# BLE.net
KiCad netlist of a schematic drawn in Altium Designer
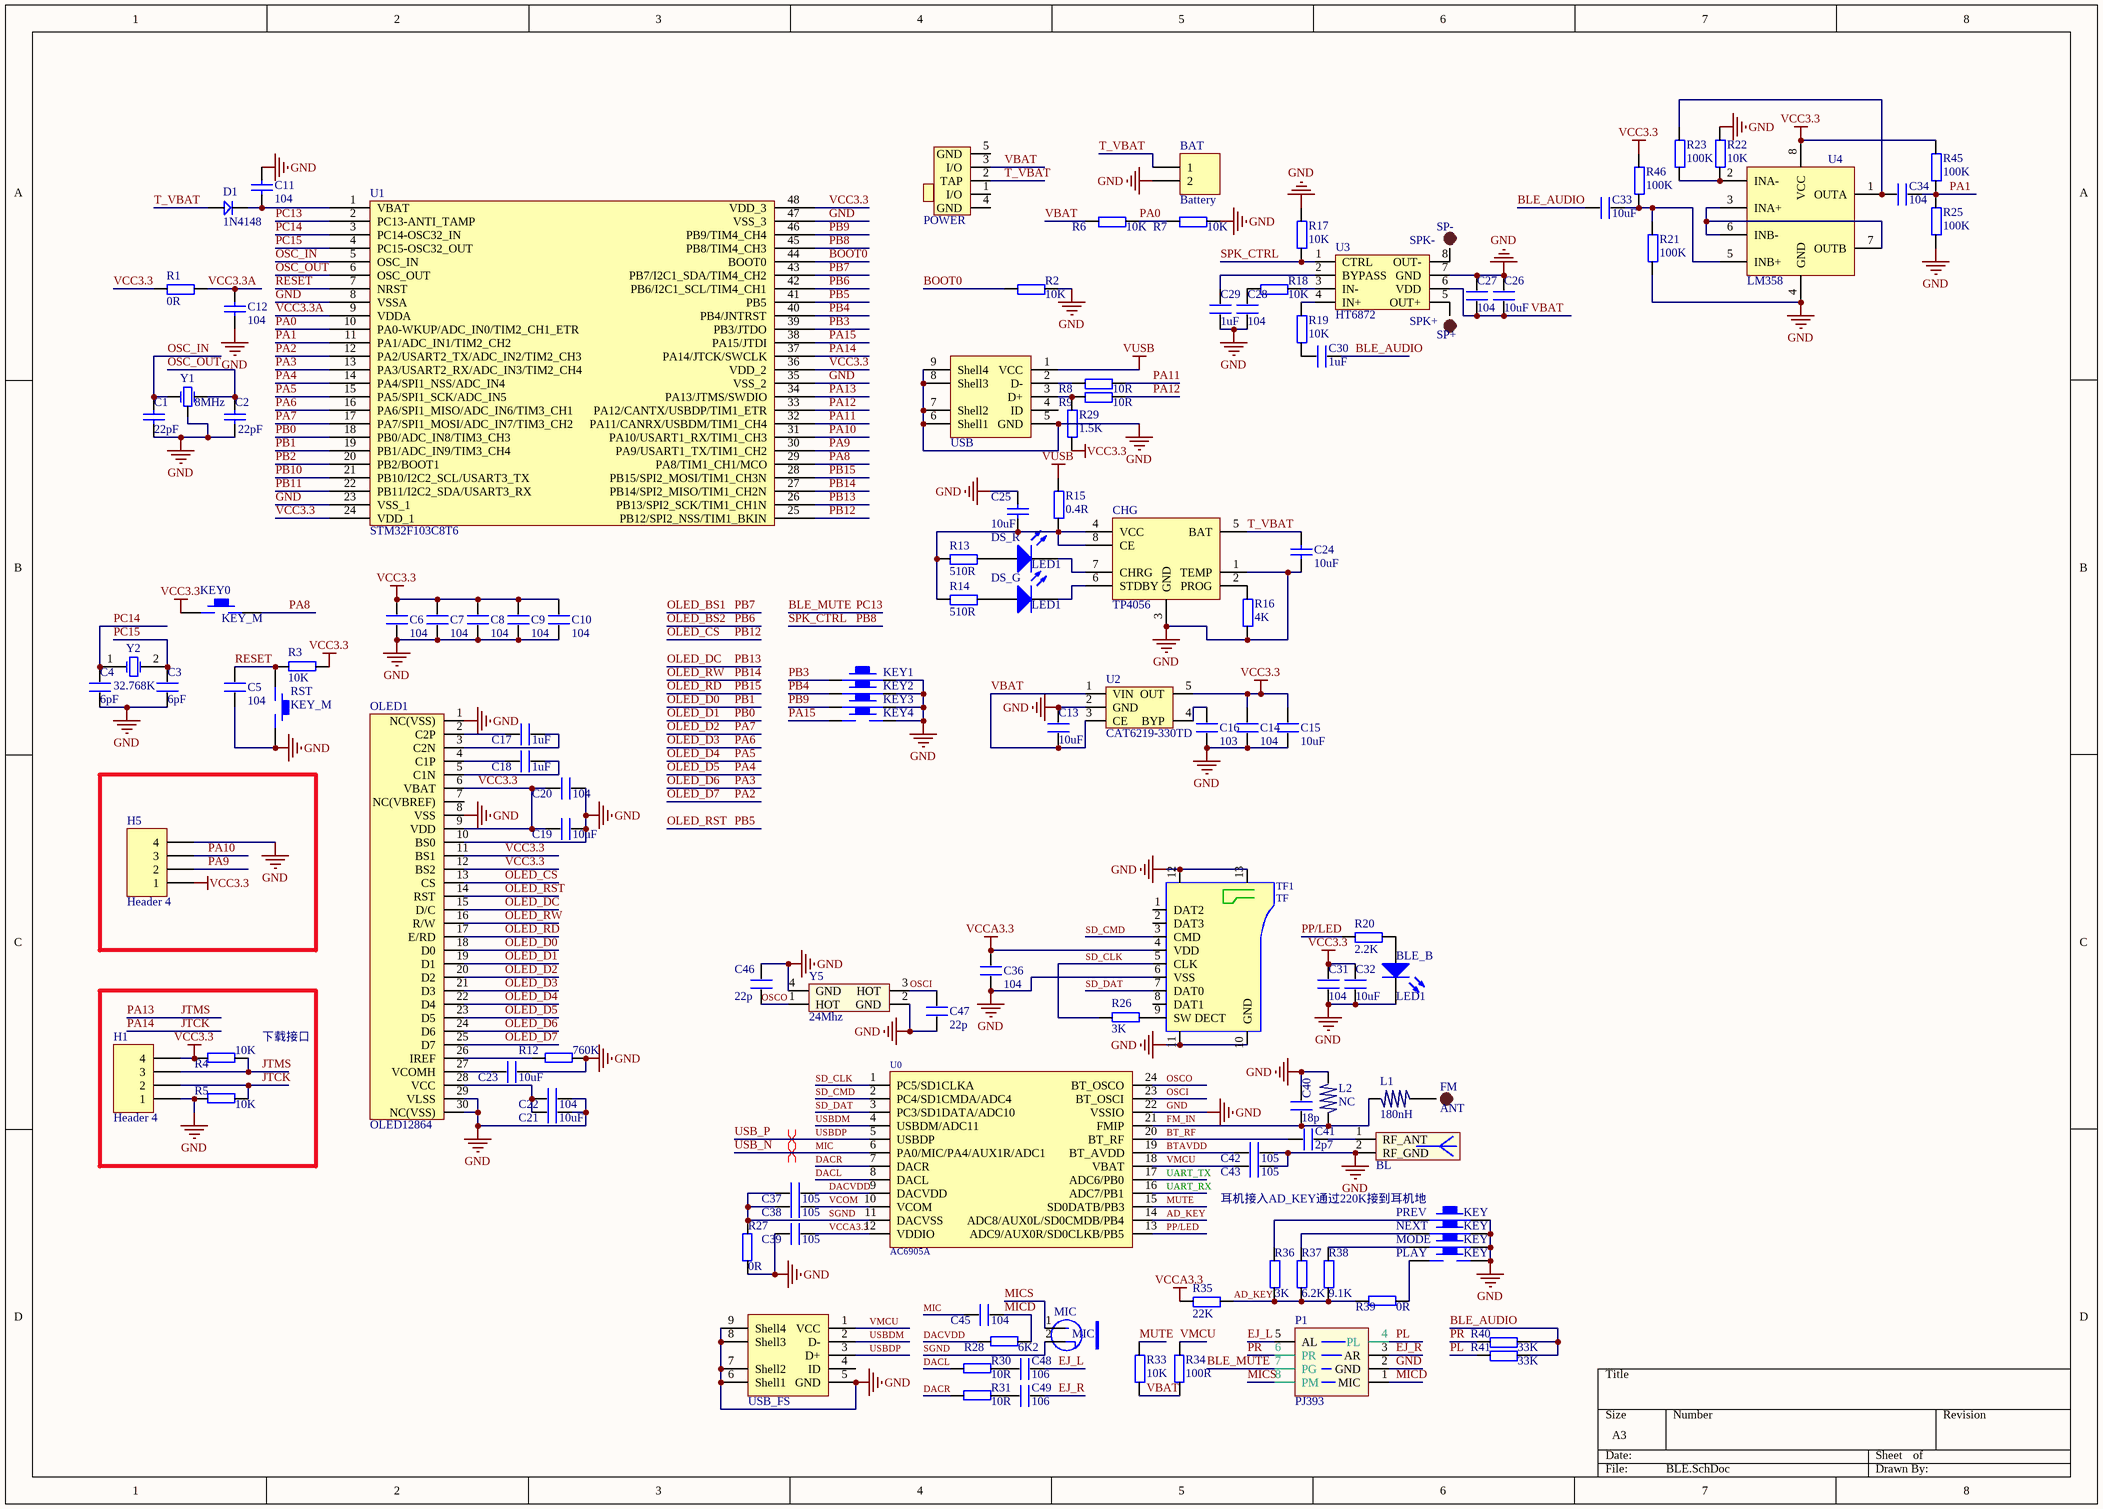
[diagram p0: BLE.SchDoc]

(export (version "E")
  (design (tool "Eeschema 10.0.6"))
  (components
    (comp (ref "BAT")
      (value "Battery")
      (footprint "HDR2.54-LI-2P")
      (description "Header, 2-Pin")
      (fields (field (name "PUBLISHER") "Altium Limited"))
      (libsource (lib "WarShip V3 STM32103封装库") (part "Header 2"))
    )
    (comp (ref "BL")
      (value "ANT-2.4G")
      (footprint "BT_ANT")
      (description "ANT,2.4G,PCB天线")
      (libsource (lib "ALIENTEK_W601_Board_V1.51") (part "ANT-2.4G"))
    )
    (comp (ref "BLE_B")
      (value "LED1")
      (footprint "LED 0805B")
      (description "Typical RED, GREEN, YELLOW, AMBER GaAs LED")
      (fields (field (name "PUBLISHER") "Altium Limited"))
      (libsource (lib "阿波罗STM32F4&F7底板封装库") (part "LED2"))
    )
    (comp (ref "C1") (value "22pF") (footprint "C 0603_M") (libsource (lib "L476") (part "CAP")))
    (comp (ref "C2") (value "22pF") (footprint "C 0603_M") (libsource (lib "L476") (part "CAP")))
    (comp (ref "C3")
      (value "6pF")
      (footprint "C 0603_M")
      (libsource (lib "WarShip V3 STM32103封装库") (part "C"))
    )
    (comp (ref "C4")
      (value "6pF")
      (footprint "C 0603_M")
      (libsource (lib "WarShip V3 STM32103封装库") (part "C"))
    )
    (comp (ref "C5")
      (value "104")
      (footprint "C 0603_M")
      (libsource (lib "WarShip V3 STM32103封装库") (part "C"))
    )
    (comp (ref "C6")
      (value "104")
      (footprint "C 0603_M")
      (libsource (lib "WarShip V3 STM32103封装库") (part "C"))
    )
    (comp (ref "C7")
      (value "104")
      (footprint "C 0603_M")
      (libsource (lib "WarShip V3 STM32103封装库") (part "C"))
    )
    (comp (ref "C8")
      (value "104")
      (footprint "C 0603_M")
      (libsource (lib "WarShip V3 STM32103封装库") (part "C"))
    )
    (comp (ref "C9")
      (value "104")
      (footprint "C 0603_M")
      (libsource (lib "WarShip V3 STM32103封装库") (part "C"))
    )
    (comp (ref "C10")
      (value "104")
      (footprint "C 0603_M")
      (libsource (lib "WarShip V3 STM32103封装库") (part "C"))
    )
    (comp (ref "C11") (value "104") (footprint "C 0603_M") (libsource (lib "L476") (part "CAP")))
    (comp (ref "C12") (value "104") (footprint "C 0603_M") (libsource (lib "L476") (part "CAP")))
    (comp (ref "C13")
      (value "10uF")
      (footprint "C 0603_M")
      (libsource (lib "WarShip V3 STM32103封装库") (part "C"))
    )
    (comp (ref "C14")
      (value "104")
      (footprint "C 0603_M")
      (libsource (lib "WarShip V3 STM32103封装库") (part "C"))
    )
    (comp (ref "C15")
      (value "10uF")
      (footprint "C 0603_M")
      (libsource (lib "WarShip V3 STM32103封装库") (part "C"))
    )
    (comp (ref "C16")
      (value "103")
      (footprint "C 0603_M")
      (libsource (lib "WarShip V3 STM32103封装库") (part "C"))
    )
    (comp (ref "C17")
      (value "1uF")
      (footprint "C 0603_M")
      (libsource (lib "WarShip V3 STM32103封装库") (part "C"))
    )
    (comp (ref "C18")
      (value "1uF")
      (footprint "C 0603_M")
      (libsource (lib "WarShip V3 STM32103封装库") (part "C"))
    )
    (comp (ref "C19")
      (value "10uF")
      (footprint "C 0603_M")
      (libsource (lib "WarShip V3 STM32103封装库") (part "C"))
    )
    (comp (ref "C20")
      (value "104")
      (footprint "C 0603_M")
      (libsource (lib "WarShip V3 STM32103封装库") (part "C"))
    )
    (comp (ref "C21")
      (value "10uF")
      (footprint "C 0603_M")
      (libsource (lib "WarShip V3 STM32103封装库") (part "C"))
    )
    (comp (ref "C22")
      (value "104")
      (footprint "C 0603_M")
      (libsource (lib "WarShip V3 STM32103封装库") (part "C"))
    )
    (comp (ref "C23")
      (value "10uF")
      (footprint "C 0603_M")
      (libsource (lib "WarShip V3 STM32103封装库") (part "C"))
    )
    (comp (ref "C24") (value "10uF") (footprint "C 0603_M") (libsource (lib "L476") (part "CAP")))
    (comp (ref "C25") (value "10uF") (footprint "C 0603_M") (libsource (lib "L476") (part "CAP")))
    (comp (ref "C26")
      (value "10uF")
      (footprint "C 0603_M")
      (libsource (lib "WarShip V3 STM32103封装库") (part "C"))
    )
    (comp (ref "C27")
      (value "104")
      (footprint "C 0603_M")
      (libsource (lib "WarShip V3 STM32103封装库") (part "C"))
    )
    (comp (ref "C28")
      (value "104")
      (footprint "C 0603_M")
      (libsource (lib "WarShip V3 STM32103封装库") (part "C"))
    )
    (comp (ref "C29")
      (value "1uF")
      (footprint "C 0603_M")
      (libsource (lib "WarShip V3 STM32103封装库") (part "C"))
    )
    (comp (ref "C30") (value "1uF") (footprint "C 0603_M") (libsource (lib "MYCOMLIB") (part "C")))
    (comp (ref "C31")
      (value "104")
      (footprint "C 0603_M")
      (libsource (lib "WarShip V3 STM32103封装库") (part "C"))
    )
    (comp (ref "C32")
      (value "10uF")
      (footprint "C 0603_M")
      (libsource (lib "WarShip V3 STM32103封装库") (part "C"))
    )
    (comp (ref "C33") (value "10uF") (footprint "C 0603_M") (libsource (lib "MYCOMLIB") (part "C")))
    (comp (ref "C34") (value "104") (footprint "C 0603_M") (libsource (lib "MYCOMLIB") (part "C")))
    (comp (ref "C36")
      (value "104")
      (footprint "C 0603_M")
      (libsource (lib "WarShip V3 STM32103封装库") (part "C"))
    )
    (comp (ref "C37")
      (value "105")
      (footprint "C 0603_M")
      (libsource (lib "WarShip V3 STM32103封装库") (part "C"))
    )
    (comp (ref "C38")
      (value "105")
      (footprint "C 0603_M")
      (libsource (lib "WarShip V3 STM32103封装库") (part "C"))
    )
    (comp (ref "C39")
      (value "105")
      (footprint "C 0603_M")
      (libsource (lib "WarShip V3 STM32103封装库") (part "C"))
    )
    (comp (ref "C40")
      (value "18p")
      (footprint "C 0603_M")
      (libsource (lib "WarShip V3 STM32103封装库") (part "C"))
    )
    (comp (ref "C41")
      (value "2p7")
      (footprint "C 0603_M")
      (libsource (lib "WarShip V3 STM32103封装库") (part "C"))
    )
    (comp (ref "C42")
      (value "105")
      (footprint "C 0603_M")
      (libsource (lib "WarShip V3 STM32103封装库") (part "C"))
    )
    (comp (ref "C43")
      (value "105")
      (footprint "C 0603_M")
      (libsource (lib "WarShip V3 STM32103封装库") (part "C"))
    )
    (comp (ref "C45")
      (value "104")
      (footprint "C 0603_M")
      (libsource (lib "WarShip V3 STM32103封装库") (part "C"))
    )
    (comp (ref "C46")
      (value "22p")
      (footprint "C 0603_M")
      (libsource (lib "WarShip V3 STM32103封装库") (part "C"))
    )
    (comp (ref "C47")
      (value "22p")
      (footprint "C 0603_M")
      (libsource (lib "WarShip V3 STM32103封装库") (part "C"))
    )
    (comp (ref "C48")
      (value "106")
      (footprint "C 0603_M")
      (libsource (lib "WarShip V3 STM32103封装库") (part "C"))
    )
    (comp (ref "C49")
      (value "106")
      (footprint "C 0603_M")
      (libsource (lib "WarShip V3 STM32103封装库") (part "C"))
    )
    (comp (ref "CHG") (value "TP4056") (footprint "SOP8_M") (libsource (lib "tp4056") (part "Component_1")))
    (comp (ref "D1")
      (value "1N4148")
      (footprint "DIODE_SOP")
      (libsource (lib "阿波罗STM32F4&F7底板封装库") (part "D"))
    )
    (comp (ref "DS_G")
      (value "LED1")
      (footprint "LED 0805G")
      (description "Typical RED, GREEN, YELLOW, AMBER GaAs LED")
      (fields (field (name "PUBLISHER") "Altium Limited"))
      (libsource (lib "阿波罗STM32F4&F7底板封装库") (part "LED2"))
    )
    (comp (ref "DS_R")
      (value "LED1")
      (footprint "LED 0805R")
      (description "Typical RED, GREEN, YELLOW, AMBER GaAs LED")
      (fields (field (name "PUBLISHER") "Altium Limited"))
      (libsource (lib "阿波罗STM32F4&F7底板封装库") (part "LED2"))
    )
    (comp (ref "FM")
      (value "ANT")
      (footprint "TP-1.5")
      (description "测试点")
      (libsource (lib "阿波罗STM32F4&F7&H7底板封装库") (part "TEST-POINT"))
    )
    (comp (ref "H1")
      (value "Header 4")
      (footprint "HDR2.54-LI-4P")
      (description "Header, 4-Pin")
      (fields (field (name "PUBLISHER") "Altium Limited"))
      (libsource (lib "WarShip V3 STM32103封装库") (part "Header 4"))
    )
    (comp (ref "H5")
      (value "Header 4")
      (footprint "HDR2.54-LI-4P")
      (description "Header, 4-Pin")
      (fields (field (name "PUBLISHER") "Altium Limited"))
      (libsource (lib "WarShip V3 STM32103封装库") (part "Header 4"))
    )
    (comp (ref "KEY0") (value "KEY_M") (footprint "TSW SMD-3*6*2.5") (libsource (lib "") (part "KEY_M_1")))
    (comp (ref "KEY1")
      (value "S-KEY-SMD-324225")
      (footprint "KEY-SOP324225")
      (description "KEY,SMD,324225")
      (libsource (lib "Pandora_STM32L4_Board_V2.4") (part "S-KEY-SMD-324225"))
    )
    (comp (ref "KEY2")
      (value "S-KEY-SMD-324225")
      (footprint "KEY-SOP324225")
      (description "KEY,SMD,324225")
      (libsource (lib "Pandora_STM32L4_Board_V2.4") (part "S-KEY-SMD-324225"))
    )
    (comp (ref "KEY3")
      (value "S-KEY-SMD-324225")
      (footprint "KEY-SOP324225")
      (description "KEY,SMD,324225")
      (libsource (lib "Pandora_STM32L4_Board_V2.4") (part "S-KEY-SMD-324225"))
    )
    (comp (ref "KEY4")
      (value "S-KEY-SMD-324225")
      (footprint "KEY-SOP324225")
      (description "KEY,SMD,324225")
      (libsource (lib "Pandora_STM32L4_Board_V2.4") (part "S-KEY-SMD-324225"))
    )
    (comp (ref "L1") (value "180nH") (footprint "L 0603") (libsource (lib "") (part "L_1")))
    (comp (ref "L2") (value "NC") (footprint "L 0603") (libsource (lib "阿波罗STM32F4&F7底板封装库") (part "L")))
    (comp (ref "MIC") (value "MIC") (footprint "mic6022") (libsource (lib "ATK-VS1053 MP3") (part "MIC")))
    (comp (ref "MODE") (value "KEY") (footprint "TSW SMD-3*6*2.5") (libsource (lib "") (part "KEY_M_1")))
    (comp (ref "NEXT") (value "KEY") (footprint "TSW SMD-3*6*2.5") (libsource (lib "") (part "KEY_M_1")))
    (comp (ref "OLED1")
      (value "OLED12864")
      (footprint "OLED_0.96")
      (libsource (lib "OLED模块封装库") (part "OLED12864"))
    )
    (comp (ref "P1") (value "PJ393") (footprint "PJ393") (libsource (lib "tp4056") (part "PJ393")))
    (comp (ref "PLAY") (value "KEY") (footprint "TSW SMD-3*6*2.5") (libsource (lib "") (part "KEY_M_1")))
    (comp (ref "POWER")
      (value "BUTTON_DIP3")
      (footprint "MSK-12C01-07")
      (description "拨动开关SS-12F44")
      (libsource (lib "Pandora_STM32L4_Board_V2.4") (part "BUTTON_DIP3"))
    )
    (comp (ref "PREV") (value "KEY") (footprint "TSW SMD-3*6*2.5") (libsource (lib "") (part "KEY_M_1")))
    (comp (ref "R1")
      (value "0R")
      (footprint "R 0603_M")
      (libsource (lib "WarShip V3 STM32103封装库") (part "R"))
    )
    (comp (ref "R2")
      (value "10K")
      (footprint "R 0603_M")
      (libsource (lib "WarShip V3 STM32103封装库") (part "R"))
    )
    (comp (ref "R3")
      (value "10K")
      (footprint "R 0603_M")
      (libsource (lib "WarShip V3 STM32103封装库") (part "R"))
    )
    (comp (ref "R4")
      (value "10K")
      (footprint "R 0603_M")
      (libsource (lib "WarShip V3 STM32103封装库") (part "R"))
    )
    (comp (ref "R5")
      (value "10K")
      (footprint "R 0603_M")
      (libsource (lib "WarShip V3 STM32103封装库") (part "R"))
    )
    (comp (ref "R6")
      (value "10K")
      (footprint "R 0603_M")
      (libsource (lib "WarShip V3 STM32103封装库") (part "R"))
    )
    (comp (ref "R7")
      (value "10K")
      (footprint "R 0603_M")
      (libsource (lib "WarShip V3 STM32103封装库") (part "R"))
    )
    (comp (ref "R8")
      (value "10R")
      (footprint "R 0603_M")
      (libsource (lib "WarShip V3 STM32103封装库") (part "R"))
    )
    (comp (ref "R9")
      (value "10R")
      (footprint "R 0603_M")
      (libsource (lib "WarShip V3 STM32103封装库") (part "R"))
    )
    (comp (ref "R12")
      (value "760K")
      (footprint "R 0603_M")
      (libsource (lib "WarShip V3 STM32103封装库") (part "R"))
    )
    (comp (ref "R13")
      (value "510R")
      (footprint "R 0603_M")
      (libsource (lib "WarShip V3 STM32103封装库") (part "R"))
    )
    (comp (ref "R14")
      (value "510R")
      (footprint "R 0603_M")
      (libsource (lib "WarShip V3 STM32103封装库") (part "R"))
    )
    (comp (ref "R15")
      (value "0.4R")
      (footprint "R 0603_M")
      (libsource (lib "WarShip V3 STM32103封装库") (part "R"))
    )
    (comp (ref "R16")
      (value "4K")
      (footprint "R 0603_M")
      (libsource (lib "WarShip V3 STM32103封装库") (part "R"))
    )
    (comp (ref "R17") (value "10K") (footprint "R 0603_M") (libsource (lib "ALIENTEK_COMPONENT") (part "R")))
    (comp (ref "R18") (value "10K") (footprint "R 0603_M") (libsource (lib "ALIENTEK_COMPONENT") (part "R")))
    (comp (ref "R19") (value "10K") (footprint "R 0603_M") (libsource (lib "ALIENTEK_COMPONENT") (part "R")))
    (comp (ref "R20")
      (value "2.2K")
      (footprint "R 0603_M")
      (libsource (lib "WarShip V3 STM32103封装库") (part "R"))
    )
    (comp (ref "R21") (value "100K") (footprint "R 0603_M") (libsource (lib "ALIENTEK_COMPONENT") (part "R")))
    (comp (ref "R22") (value "10K") (footprint "R 0603_M") (libsource (lib "ALIENTEK_COMPONENT") (part "R")))
    (comp (ref "R23") (value "100K") (footprint "R 0603_M") (libsource (lib "ALIENTEK_COMPONENT") (part "R")))
    (comp (ref "R25") (value "100K") (footprint "R 0603_M") (libsource (lib "ALIENTEK_COMPONENT") (part "R")))
    (comp (ref "R26")
      (value "3K")
      (footprint "R 0603_M")
      (libsource (lib "WarShip V3 STM32103封装库") (part "R"))
    )
    (comp (ref "R27")
      (value "0R")
      (footprint "R 0603_M")
      (libsource (lib "WarShip V3 STM32103封装库") (part "R"))
    )
    (comp (ref "R28")
      (value "6K2")
      (footprint "R 0603_M")
      (libsource (lib "WarShip V3 STM32103封装库") (part "R"))
    )
    (comp (ref "R29")
      (value "1.5K")
      (footprint "R 0603_M")
      (libsource (lib "WarShip V3 STM32103封装库") (part "R"))
    )
    (comp (ref "R30")
      (value "10R")
      (footprint "R 0603_M")
      (libsource (lib "WarShip V3 STM32103封装库") (part "R"))
    )
    (comp (ref "R31")
      (value "10R")
      (footprint "R 0603_M")
      (libsource (lib "WarShip V3 STM32103封装库") (part "R"))
    )
    (comp (ref "R33")
      (value "10K")
      (footprint "R 0603_M")
      (libsource (lib "WarShip V3 STM32103封装库") (part "R"))
    )
    (comp (ref "R34")
      (value "100R")
      (footprint "R 0603_M")
      (libsource (lib "WarShip V3 STM32103封装库") (part "R"))
    )
    (comp (ref "R35")
      (value "22K")
      (footprint "R 0603_M")
      (libsource (lib "WarShip V3 STM32103封装库") (part "R"))
    )
    (comp (ref "R36")
      (value "3K")
      (footprint "R 0603_M")
      (libsource (lib "WarShip V3 STM32103封装库") (part "R"))
    )
    (comp (ref "R37")
      (value "6.2K")
      (footprint "R 0603_M")
      (libsource (lib "WarShip V3 STM32103封装库") (part "R"))
    )
    (comp (ref "R38")
      (value "9.1K")
      (footprint "R 0603_M")
      (libsource (lib "WarShip V3 STM32103封装库") (part "R"))
    )
    (comp (ref "R39")
      (value "0R")
      (footprint "R 0603_M")
      (libsource (lib "WarShip V3 STM32103封装库") (part "R"))
    )
    (comp (ref "R40")
      (value "33K")
      (footprint "R 0603_M")
      (libsource (lib "WarShip V3 STM32103封装库") (part "R"))
    )
    (comp (ref "R41")
      (value "33K")
      (footprint "R 0603_M")
      (libsource (lib "WarShip V3 STM32103封装库") (part "R"))
    )
    (comp (ref "R45") (value "100K") (footprint "R 0603_M") (libsource (lib "ALIENTEK_COMPONENT") (part "R")))
    (comp (ref "R46") (value "100K") (footprint "R 0603_M") (libsource (lib "ALIENTEK_COMPONENT") (part "R")))
    (comp (ref "RST")
      (value "KEY_M")
      (footprint "TSW SMD-3*6*2.5")
      (libsource (lib "STM32F429核心板封装库") (part "KEY_M"))
    )
    (comp (ref "SP+")
      (value "SPK+")
      (footprint "TP-1.5")
      (description "测试点")
      (libsource (lib "ALIENTEK_COMPONENT") (part "TEST-POINT"))
    )
    (comp (ref "SP-")
      (value "SPK-")
      (footprint "TP-1.5")
      (description "测试点")
      (libsource (lib "ALIENTEK_COMPONENT") (part "TEST-POINT"))
    )
    (comp (ref "TF1") (value "TF") (footprint "TF") (libsource (lib "AC6905A") (part "TF")))
    (comp (ref "U0")
      (value "AC6905A")
      (footprint "SSOP24")
      (libsource (lib "AC6905A") (part "Component_1_1"))
    )
    (comp (ref "U1")
      (value "STM32F103C8T6")
      (footprint "LQFP-48PIN")
      (libsource (lib "Pandora_STM32L4_Board_V2.4") (part "U-STM32F103C8T6"))
    )
    (comp (ref "U2")
      (value "CAT6219-330TD")
      (footprint "SOT23-5L")
      (description "3.3V 500mA LDO")
      (libsource (lib "STM32H743核心板封装库") (part "CAT6219-330TD"))
    )
    (comp (ref "U3")
      (value "HT6872")
      (footprint "SOP8_M")
      (description "HT6871")
      (libsource (lib "WarShip V3 STM32103封装库") (part "HT6871"))
    )
    (comp (ref "U4") (value "LM358") (footprint "SOP8_M") (libsource (lib "tp4056") (part "Component_2")))
    (comp (ref "USB")
      (value "J-MICRO-USB-5S")
      (footprint "USB-AB-5S")
      (description "Micro USB 5.9有柱脚长1.25加长针")
      (libsource (lib "Pandora_STM32L4_Board_V2.4") (part "J-MICRO-USB-5S"))
    )
    (comp (ref "USB_FS")
      (value "J-MICRO-USB-5S")
      (footprint "USB-AB-5S")
      (description "Micro USB 5.9有柱脚长1.25加长针")
      (libsource (lib "Pandora_STM32L4_Board_V2.4") (part "J-MICRO-USB-5S"))
    )
    (comp (ref "Y1")
      (value "8MHz")
      (footprint "Y-XTAL-3215-3P")
      (description "XTAL,3215,8MHz")
      (libsource (lib "Pandora_STM32L4_Board_V2.4") (part "Y-3215-8M"))
    )
    (comp (ref "Y2")
      (value "32.768K")
      (footprint "OSC 3215-2P")
      (description "Crystal Oscillator")
      (fields (field (name "PUBLISHER") "Altium Limited"))
      (libsource (lib "WarShip V3 STM32103封装库") (part "XTAL"))
    )
    (comp (ref "Y5")
      (value "24Mhz")
      (footprint "OSC 3225-4P")
      (description "3225贴片无源晶振")
      (libsource (lib "STM32F767核心板封装库") (part "XTAL_3225"))
    )
  )
  (nets
    (net (code "1") (name "/AD_KEY") (class "Default")
      (node (ref "R35") (pin "2") (pintype "passive"))
      (node (ref "R36") (pin "1") (pintype "passive"))
      (node (ref "R37") (pin "1") (pintype "passive"))
      (node (ref "R38") (pin "1") (pintype "passive"))
      (node (ref "R39") (pin "2") (pintype "passive"))
      (node (ref "U0") (pin "14") (pinfunction "ADC8/AUX0L/SD0CMDB/PB4_14") (pintype "passive"))
    )
    (net (code "2") (name "/BLE_AUDIO") (class "Default")
      (node (ref "C30") (pin "2") (pintype "passive"))
      (node (ref "C33") (pin "1") (pintype "passive"))
      (node (ref "R40") (pin "2") (pintype "passive"))
      (node (ref "R41") (pin "2") (pintype "passive"))
    )
    (net (code "3") (name "/BLE_MUTE") (class "Default")
      (node (ref "P1") (pin "7") (pinfunction "PG_7") (pintype "passive"))
      (node (ref "U1") (pin "2") (pinfunction "PC13-ANTI_TAMP_2") (pintype "passive"))
    )
    (net (code "4") (name "/BOOT0") (class "Default")
      (node (ref "R2") (pin "1") (pintype "passive"))
      (node (ref "U1") (pin "44") (pinfunction "BOOT0_44") (pintype "passive"))
    )
    (net (code "5") (name "/BTAVDD") (class "Default")
      (node (ref "C42") (pin "1") (pintype "passive"))
      (node (ref "U0") (pin "19") (pinfunction "BT_AVDD_19") (pintype "passive"))
    )
    (net (code "6") (name "/BT_RF") (class "Default")
      (node (ref "C41") (pin "1") (pintype "passive"))
      (node (ref "U0") (pin "20") (pinfunction "BT_RF_20") (pintype "passive"))
    )
    (net (code "7") (name "/DACL") (class "Default")
      (node (ref "R30") (pin "2") (pintype "passive"))
      (node (ref "U0") (pin "8") (pinfunction "DACL_8") (pintype "passive"))
    )
    (net (code "8") (name "/DACR") (class "Default")
      (node (ref "R31") (pin "2") (pintype "passive"))
      (node (ref "U0") (pin "7") (pinfunction "DACR_7") (pintype "passive"))
    )
    (net (code "9") (name "/DACVDD") (class "Default")
      (node (ref "C37") (pin "1") (pintype "passive"))
      (node (ref "R28") (pin "2") (pintype "passive"))
      (node (ref "U0") (pin "9") (pinfunction "DACVDD_9") (pintype "passive"))
    )
    (net (code "10") (name "/EJ_L") (class "Default")
      (node (ref "C48") (pin "2") (pintype "passive"))
      (node (ref "P1") (pin "5") (pinfunction "AL_5") (pintype "passive"))
    )
    (net (code "11") (name "/EJ_R") (class "Default")
      (node (ref "C49") (pin "2") (pintype "passive"))
      (node (ref "P1") (pin "3") (pinfunction "AR_3") (pintype "passive"))
    )
    (net (code "12") (name "/FM_IN") (class "Default")
      (node (ref "C40") (pin "2") (pintype "passive"))
      (node (ref "L1") (pin "1") (pintype "passive"))
      (node (ref "L2") (pin "2") (pintype "passive"))
      (node (ref "U0") (pin "21") (pinfunction "FMIP_21") (pintype "passive"))
    )
    (net (code "13") (name "/JTCK") (class "Default")
      (node (ref "H1") (pin "2") (pinfunction "2_2") (pintype "passive"))
      (node (ref "R5") (pin "1") (pintype "passive"))
      (node (ref "U1") (pin "37") (pinfunction "PA14/JTCK/SWCLK_37") (pintype "passive"))
    )
    (net (code "14") (name "/JTMS") (class "Default")
      (node (ref "H1") (pin "3") (pinfunction "3_3") (pintype "passive"))
      (node (ref "R4") (pin "1") (pintype "passive"))
      (node (ref "U1") (pin "34") (pinfunction "PA13/JTMS/SWDIO_34") (pintype "passive"))
    )
    (net (code "15") (name "/MIC") (class "Default")
      (node (ref "C45") (pin "1") (pintype "passive"))
      (node (ref "U0") (pin "6") (pinfunction "PA0/MIC/PA4/AUX1R/ADC1_6") (pintype "passive"))
    )
    (net (code "16") (name "/MICD") (class "Default")
      (node (ref "C45") (pin "2") (pintype "passive"))
      (node (ref "P1") (pin "1") (pinfunction "MIC_1") (pintype "passive"))
      (node (ref "R28") (pin "1") (pintype "passive"))
    )
    (net (code "17") (name "/MICS") (class "Default")
      (node (ref "MIC") (pin "1") (pinfunction "VCC_1") (pintype "passive"))
      (node (ref "P1") (pin "8") (pinfunction "PM_8") (pintype "passive"))
    )
    (net (code "18") (name "/MUTE") (class "Default")
      (node (ref "R33") (pin "2") (pintype "passive"))
      (node (ref "U0") (pin "15") (pinfunction "SD0DATB/PB3_15") (pintype "passive"))
    )
    (net (code "19") (name "/OLED_BS1") (class "Default")
      (node (ref "U1") (pin "43") (pinfunction "PB7/I2C1_SDA/TIM4_CH2_43") (pintype "passive"))
    )
    (net (code "20") (name "/OLED_BS2") (class "Default")
      (node (ref "U1") (pin "42") (pinfunction "PB6/I2C1_SCL/TIM4_CH1_42") (pintype "passive"))
    )
    (net (code "21") (name "/OLED_CS") (class "Default")
      (node (ref "OLED1") (pin "13") (pinfunction "CS_13") (pintype "passive"))
      (node (ref "U1") (pin "25") (pinfunction "PB12/SPI2_NSS/TIM1_BKIN_25") (pintype "passive"))
    )
    (net (code "22") (name "/OLED_D0") (class "Default")
      (node (ref "OLED1") (pin "18") (pinfunction "D0_18") (pintype "passive"))
      (node (ref "U1") (pin "19") (pinfunction "PB1/ADC_IN9/TIM3_CH4_19") (pintype "passive"))
    )
    (net (code "23") (name "/OLED_D1") (class "Default")
      (node (ref "OLED1") (pin "19") (pinfunction "D1_19") (pintype "passive"))
      (node (ref "U1") (pin "18") (pinfunction "PB0/ADC_IN8/TIM3_CH3_18") (pintype "passive"))
    )
    (net (code "24") (name "/OLED_D2") (class "Default")
      (node (ref "OLED1") (pin "20") (pinfunction "D2_20") (pintype "passive"))
      (node (ref "U1") (pin "17") (pinfunction "PA7/SPI1_MOSI/ADC_IN7/TIM3_CH2_17") (pintype "passive"))
    )
    (net (code "25") (name "/OLED_D3") (class "Default")
      (node (ref "OLED1") (pin "21") (pinfunction "D3_21") (pintype "passive"))
      (node (ref "U1") (pin "16") (pinfunction "PA6/SPI1_MISO/ADC_IN6/TIM3_CH1_16") (pintype "passive"))
    )
    (net (code "26") (name "/OLED_D4") (class "Default")
      (node (ref "OLED1") (pin "22") (pinfunction "D4_22") (pintype "passive"))
      (node (ref "U1") (pin "15") (pinfunction "PA5/SPI1_SCK/ADC_IN5_15") (pintype "passive"))
    )
    (net (code "27") (name "/OLED_D5") (class "Default")
      (node (ref "OLED1") (pin "23") (pinfunction "D5_23") (pintype "passive"))
      (node (ref "U1") (pin "14") (pinfunction "PA4/SPI1_NSS/ADC_IN4_14") (pintype "passive"))
    )
    (net (code "28") (name "/OLED_D6") (class "Default")
      (node (ref "OLED1") (pin "24") (pinfunction "D6_24") (pintype "passive"))
      (node (ref "U1") (pin "13") (pinfunction "PA3/USART2_RX/ADC_IN3/TIM2_CH4_13") (pintype "passive"))
    )
    (net (code "29") (name "/OLED_D7") (class "Default")
      (node (ref "OLED1") (pin "25") (pinfunction "D7_25") (pintype "passive"))
      (node (ref "U1") (pin "12") (pinfunction "PA2/USART2_TX/ADC_IN2/TIM2_CH3_12") (pintype "passive"))
    )
    (net (code "30") (name "/OLED_DC") (class "Default")
      (node (ref "OLED1") (pin "15") (pinfunction "D/C_15") (pintype "passive"))
      (node (ref "U1") (pin "26") (pinfunction "PB13/SPI2_SCK/TIM1_CH1N_26") (pintype "passive"))
    )
    (net (code "31") (name "/OLED_RD") (class "Default")
      (node (ref "OLED1") (pin "17") (pinfunction "E/RD_17") (pintype "passive"))
      (node (ref "U1") (pin "28") (pinfunction "PB15/SPI2_MOSI/TIM1_CH3N_28") (pintype "passive"))
    )
    (net (code "32") (name "/OLED_RST") (class "Default")
      (node (ref "OLED1") (pin "14") (pinfunction "RST_14") (pintype "passive"))
      (node (ref "U1") (pin "41") (pinfunction "PB5_41") (pintype "passive"))
    )
    (net (code "33") (name "/OLED_RW") (class "Default")
      (node (ref "OLED1") (pin "16") (pinfunction "R/W_16") (pintype "passive"))
      (node (ref "U1") (pin "27") (pinfunction "PB14/SPI2_MISO/TIM1_CH2N_27") (pintype "passive"))
    )
    (net (code "34") (name "/OSCI") (class "Default")
      (node (ref "C47") (pin "2") (pintype "passive"))
      (node (ref "U0") (pin "23") (pinfunction "BT_OSCI_23") (pintype "passive"))
      (node (ref "Y5") (pin "3") (pinfunction "HOT_3") (pintype "passive"))
    )
    (net (code "35") (name "/OSCO") (class "Default")
      (node (ref "C46") (pin "2") (pintype "passive"))
      (node (ref "U0") (pin "24") (pinfunction "BT_OSCO_24") (pintype "passive"))
      (node (ref "Y5") (pin "1") (pinfunction "HOT_1") (pintype "passive"))
    )
    (net (code "36") (name "/OSC_IN") (class "Default")
      (node (ref "C1") (pin "2") (pinfunction "2_2") (pintype "passive"))
      (node (ref "U1") (pin "5") (pinfunction "OSC_IN_5") (pintype "passive"))
      (node (ref "Y1") (pin "1") (pinfunction "OSC1_1") (pintype "passive"))
    )
    (net (code "37") (name "/OSC_OUT") (class "Default")
      (node (ref "C2") (pin "2") (pinfunction "2_2") (pintype "passive"))
      (node (ref "U1") (pin "6") (pinfunction "OSC_OUT_6") (pintype "passive"))
      (node (ref "Y1") (pin "3") (pinfunction "OSC2_3") (pintype "passive"))
    )
    (net (code "38") (name "/PA0") (class "Default")
      (node (ref "R6") (pin "2") (pintype "passive"))
      (node (ref "R7") (pin "1") (pintype "passive"))
      (node (ref "U1") (pin "10") (pinfunction "PA0-WKUP/ADC_IN0/TIM2_CH1_ETR_10") (pintype "passive"))
    )
    (net (code "39") (name "/PA1") (class "Default")
      (node (ref "C34") (pin "2") (pintype "passive"))
      (node (ref "R25") (pin "2") (pintype "passive"))
      (node (ref "R45") (pin "1") (pintype "passive"))
      (node (ref "U1") (pin "11") (pinfunction "PA1/ADC_IN1/TIM2_CH2_11") (pintype "passive"))
    )
    (net (code "40") (name "/PA8") (class "Default")
      (node (ref "KEY0") (pin "2") (pinfunction "2_2") (pintype "passive"))
      (node (ref "U1") (pin "29") (pinfunction "PA8/TIM1_CH1/MCO_29") (pintype "passive"))
    )
    (net (code "41") (name "/PA9") (class "Default")
      (node (ref "H5") (pin "2") (pinfunction "2_2") (pintype "passive"))
      (node (ref "U1") (pin "30") (pinfunction "PA9/USART1_TX/TIM1_CH2_30") (pintype "passive"))
    )
    (net (code "42") (name "/PA10") (class "Default")
      (node (ref "H5") (pin "3") (pinfunction "3_3") (pintype "passive"))
      (node (ref "U1") (pin "31") (pinfunction "PA10/USART1_RX/TIM1_CH3_31") (pintype "passive"))
    )
    (net (code "43") (name "/PA11") (class "Default")
      (node (ref "R8") (pin "2") (pintype "passive"))
      (node (ref "U1") (pin "32") (pinfunction "PA11/CANRX/USBDM/TIM1_CH4_32") (pintype "passive"))
    )
    (net (code "44") (name "/PA12") (class "Default")
      (node (ref "R9") (pin "2") (pintype "passive"))
      (node (ref "U1") (pin "33") (pinfunction "PA12/CANTX/USBDP/TIM1_ETR_33") (pintype "passive"))
    )
    (net (code "45") (name "/PA15") (class "Default")
      (node (ref "KEY4") (pin "1") (pinfunction "1_1") (pintype "passive"))
      (node (ref "U1") (pin "38") (pinfunction "PA15/JTDI_38") (pintype "passive"))
    )
    (net (code "46") (name "/PB2") (class "Default")
      (node (ref "U1") (pin "20") (pinfunction "PB2/BOOT1_20") (pintype "passive"))
    )
    (net (code "47") (name "/PB3") (class "Default")
      (node (ref "KEY1") (pin "1") (pinfunction "1_1") (pintype "passive"))
      (node (ref "U1") (pin "39") (pinfunction "PB3/JTDO_39") (pintype "passive"))
    )
    (net (code "48") (name "/PB4") (class "Default")
      (node (ref "KEY2") (pin "1") (pinfunction "1_1") (pintype "passive"))
      (node (ref "U1") (pin "40") (pinfunction "PB4/JNTRST_40") (pintype "passive"))
    )
    (net (code "49") (name "/PB8") (class "Default")
      (node (ref "R17") (pin "1") (pintype "passive"))
      (node (ref "U1") (pin "45") (pinfunction "PB8/TIM4_CH3_45") (pintype "passive"))
      (node (ref "U3") (pin "1") (pinfunction "CTRL_1") (pintype "passive"))
    )
    (net (code "50") (name "/PB9") (class "Default")
      (node (ref "KEY3") (pin "1") (pinfunction "1_1") (pintype "passive"))
      (node (ref "U1") (pin "46") (pinfunction "PB9/TIM4_CH4_46") (pintype "passive"))
    )
    (net (code "51") (name "/PB10") (class "Default")
      (node (ref "U1") (pin "21") (pinfunction "PB10/I2C2_SCL/USART3_TX_21") (pintype "passive"))
    )
    (net (code "52") (name "/PB11") (class "Default")
      (node (ref "U1") (pin "22") (pinfunction "PB11/I2C2_SDA/USART3_RX_22") (pintype "passive"))
    )
    (net (code "53") (name "/PC14") (class "Default")
      (node (ref "C4") (pin "2") (pintype "passive"))
      (node (ref "U1") (pin "3") (pinfunction "PC14-OSC32_IN_3") (pintype "passive"))
      (node (ref "Y2") (pin "1") (pinfunction "OSC1_1") (pintype "passive"))
    )
    (net (code "54") (name "/PC15") (class "Default")
      (node (ref "C3") (pin "2") (pintype "passive"))
      (node (ref "U1") (pin "4") (pinfunction "PC15-OSC32_OUT_4") (pintype "passive"))
      (node (ref "Y2") (pin "2") (pinfunction "OSC2_2") (pintype "passive"))
    )
    (net (code "55") (name "/PL") (class "Default")
      (node (ref "P1") (pin "4") (pinfunction "PL_4") (pintype "passive"))
      (node (ref "R41") (pin "1") (pintype "passive"))
    )
    (net (code "56") (name "/PP{slash}LED") (class "Default")
      (node (ref "R20") (pin "1") (pintype "passive"))
      (node (ref "U0") (pin "13") (pinfunction "ADC9/AUX0R/SD0CLKB/PB5_13") (pintype "passive"))
    )
    (net (code "57") (name "/PR") (class "Default")
      (node (ref "P1") (pin "6") (pinfunction "PR_6") (pintype "passive"))
      (node (ref "R40") (pin "1") (pintype "passive"))
    )
    (net (code "58") (name "/RESET") (class "Default")
      (node (ref "C5") (pin "2") (pintype "passive"))
      (node (ref "R3") (pin "2") (pintype "passive"))
      (node (ref "RST") (pin "1") (pinfunction "1_1") (pintype "passive"))
      (node (ref "U1") (pin "7") (pinfunction "NRST_7") (pintype "passive"))
    )
    (net (code "59") (name "/SD_CLK") (class "Default")
      (node (ref "R26") (pin "2") (pintype "passive"))
      (node (ref "TF1") (pin "5") (pinfunction "CLK_5") (pintype "passive"))
      (node (ref "U0") (pin "1") (pinfunction "PC5/SD1CLKA_1") (pintype "passive"))
    )
    (net (code "60") (name "/SD_CMD") (class "Default")
      (node (ref "TF1") (pin "3") (pinfunction "CMD_3") (pintype "passive"))
      (node (ref "U0") (pin "2") (pinfunction "PC4/SD1CMDA/ADC4_2") (pintype "passive"))
    )
    (net (code "61") (name "/SD_DAT") (class "Default")
      (node (ref "TF1") (pin "7") (pinfunction "DAT0_7") (pintype "passive"))
      (node (ref "U0") (pin "3") (pinfunction "PC3/SD1DATA/ADC10_3") (pintype "passive"))
    )
    (net (code "62") (name "/SGND") (class "Default")
      (node (ref "C37") (pin "2") (pintype "passive"))
      (node (ref "C38") (pin "2") (pintype "passive"))
      (node (ref "MIC") (pin "2") (pinfunction "GND_2") (pintype "passive"))
      (node (ref "R27") (pin "1") (pintype "passive"))
      (node (ref "U0") (pin "11") (pinfunction "DACVSS_11") (pintype "passive"))
    )
    (net (code "63") (name "/T_VBAT") (class "Default")
      (node (ref "BAT") (pin "1") (pinfunction "1_1") (pintype "passive"))
      (node (ref "C24") (pin "1") (pinfunction "1_1") (pintype "passive"))
      (node (ref "CHG") (pin "5") (pinfunction "BAT_5") (pintype "passive"))
      (node (ref "D1") (pin "1") (pintype "passive"))
      (node (ref "POWER") (pin "2") (pinfunction "TAP_2") (pintype "passive"))
    )
    (net (code "64") (name "/UART_RX") (class "Default")
      (node (ref "U0") (pin "16") (pinfunction "ADC7/PB1_16") (pintype "passive"))
    )
    (net (code "65") (name "/UART_TX") (class "Default")
      (node (ref "U0") (pin "17") (pinfunction "ADC6/PB0_17") (pintype "passive"))
    )
    (net (code "66") (name "/USBDM") (class "Default")
      (node (ref "U0") (pin "4") (pinfunction "USBDM/ADC11_4") (pintype "passive"))
      (node (ref "USB_FS") (pin "2") (pinfunction "D-_2") (pintype "passive"))
    )
    (net (code "67") (name "/USBDP") (class "Default")
      (node (ref "U0") (pin "5") (pinfunction "USBDP_5") (pintype "passive"))
      (node (ref "USB_FS") (pin "3") (pinfunction "D+_3") (pintype "passive"))
    )
    (net (code "68") (name "/VBAT") (class "Default")
      (node (ref "C13") (pin "1") (pintype "passive"))
      (node (ref "C26") (pin "1") (pintype "passive"))
      (node (ref "C27") (pin "1") (pintype "passive"))
      (node (ref "POWER") (pin "3") (pinfunction "I/O_3") (pintype "passive"))
      (node (ref "R33") (pin "1") (pintype "passive"))
      (node (ref "R34") (pin "2") (pintype "passive"))
      (node (ref "R6") (pin "1") (pintype "passive"))
      (node (ref "U2") (pin "1") (pinfunction "VIN_1") (pintype "passive"))
      (node (ref "U2") (pin "3") (pinfunction "CE_3") (pintype "passive"))
      (node (ref "U3") (pin "6") (pinfunction "VDD_6") (pintype "passive"))
    )
    (net (code "69") (name "/VCC3.3A") (class "Default")
      (node (ref "C12") (pin "2") (pinfunction "2_2") (pintype "passive"))
      (node (ref "R1") (pin "2") (pintype "passive"))
      (node (ref "U1") (pin "9") (pinfunction "VDDA_9") (pintype "passive"))
    )
    (net (code "70") (name "/VCOM") (class "Default")
      (node (ref "C38") (pin "1") (pintype "passive"))
      (node (ref "U0") (pin "10") (pinfunction "VCOM_10") (pintype "passive"))
    )
    (net (code "71") (name "/VMCU") (class "Default")
      (node (ref "C43") (pin "1") (pintype "passive"))
      (node (ref "R34") (pin "1") (pintype "passive"))
      (node (ref "U0") (pin "18") (pinfunction "VBAT_18") (pintype "passive"))
      (node (ref "USB_FS") (pin "1") (pinfunction "VCC_1") (pintype "passive"))
    )
    (net (code "72") (name "GND") (class "Default")
      (node (ref "BAT") (pin "2") (pinfunction "2_2") (pintype "passive"))
      (node (ref "BL") (pin "2") (pinfunction "RF_GND_2") (pintype "passive"))
      (node (ref "BLE_B") (pin "2") (pinfunction "K_2") (pintype "passive"))
      (node (ref "C1") (pin "1") (pinfunction "1_1") (pintype "passive"))
      (node (ref "C10") (pin "1") (pintype "passive"))
      (node (ref "C11") (pin "2") (pinfunction "2_2") (pintype "passive"))
      (node (ref "C12") (pin "1") (pinfunction "1_1") (pintype "passive"))
      (node (ref "C13") (pin "2") (pintype "passive"))
      (node (ref "C14") (pin "1") (pintype "passive"))
      (node (ref "C15") (pin "1") (pintype "passive"))
      (node (ref "C16") (pin "1") (pintype "passive"))
      (node (ref "C19") (pin "1") (pintype "passive"))
      (node (ref "C2") (pin "1") (pinfunction "1_1") (pintype "passive"))
      (node (ref "C20") (pin "1") (pintype "passive"))
      (node (ref "C21") (pin "1") (pintype "passive"))
      (node (ref "C22") (pin "1") (pintype "passive"))
      (node (ref "C23") (pin "1") (pintype "passive"))
      (node (ref "C24") (pin "2") (pinfunction "2_2") (pintype "passive"))
      (node (ref "C25") (pin "2") (pinfunction "2_2") (pintype "passive"))
      (node (ref "C26") (pin "2") (pintype "passive"))
      (node (ref "C27") (pin "2") (pintype "passive"))
      (node (ref "C28") (pin "1") (pintype "passive"))
      (node (ref "C29") (pin "1") (pintype "passive"))
      (node (ref "C3") (pin "1") (pintype "passive"))
      (node (ref "C31") (pin "1") (pintype "passive"))
      (node (ref "C32") (pin "1") (pintype "passive"))
      (node (ref "C36") (pin "1") (pintype "passive"))
      (node (ref "C39") (pin "2") (pintype "passive"))
      (node (ref "C4") (pin "1") (pintype "passive"))
      (node (ref "C40") (pin "1") (pintype "passive"))
      (node (ref "C42") (pin "2") (pintype "passive"))
      (node (ref "C43") (pin "2") (pintype "passive"))
      (node (ref "C46") (pin "1") (pintype "passive"))
      (node (ref "C47") (pin "1") (pintype "passive"))
      (node (ref "C5") (pin "1") (pintype "passive"))
      (node (ref "C6") (pin "1") (pintype "passive"))
      (node (ref "C7") (pin "1") (pintype "passive"))
      (node (ref "C8") (pin "1") (pintype "passive"))
      (node (ref "C9") (pin "1") (pintype "passive"))
      (node (ref "CHG") (pin "1") (pinfunction "TEMP_1") (pintype "passive"))
      (node (ref "CHG") (pin "3") (pinfunction "GND_3") (pintype "passive"))
      (node (ref "H1") (pin "1") (pinfunction "1_1") (pintype "passive"))
      (node (ref "H5") (pin "4") (pinfunction "4_4") (pintype "passive"))
      (node (ref "KEY1") (pin "2") (pinfunction "2_2") (pintype "passive"))
      (node (ref "KEY2") (pin "2") (pinfunction "2_2") (pintype "passive"))
      (node (ref "KEY3") (pin "2") (pinfunction "2_2") (pintype "passive"))
      (node (ref "KEY4") (pin "2") (pinfunction "2_2") (pintype "passive"))
      (node (ref "L2") (pin "1") (pintype "passive"))
      (node (ref "MODE") (pin "2") (pinfunction "2_2") (pintype "passive"))
      (node (ref "NEXT") (pin "2") (pinfunction "2_2") (pintype "passive"))
      (node (ref "OLED1") (pin "1") (pinfunction "NC(VSS)_1") (pintype "passive"))
      (node (ref "OLED1") (pin "10") (pinfunction "BS0_10") (pintype "passive"))
      (node (ref "OLED1") (pin "29") (pinfunction "VLSS_29") (pintype "passive"))
      (node (ref "OLED1") (pin "30") (pinfunction "NC(VSS)_30") (pintype "passive"))
      (node (ref "OLED1") (pin "8") (pinfunction "VSS_8") (pintype "passive"))
      (node (ref "P1") (pin "2") (pinfunction "GND_2") (pintype "passive"))
      (node (ref "PLAY") (pin "2") (pinfunction "2_2") (pintype "passive"))
      (node (ref "PREV") (pin "2") (pinfunction "2_2") (pintype "passive"))
      (node (ref "R12") (pin "1") (pintype "passive"))
      (node (ref "R16") (pin "1") (pintype "passive"))
      (node (ref "R17") (pin "2") (pintype "passive"))
      (node (ref "R2") (pin "2") (pintype "passive"))
      (node (ref "R21") (pin "1") (pintype "passive"))
      (node (ref "R22") (pin "2") (pintype "passive"))
      (node (ref "R25") (pin "1") (pintype "passive"))
      (node (ref "R27") (pin "2") (pintype "passive"))
      (node (ref "R5") (pin "2") (pintype "passive"))
      (node (ref "R7") (pin "2") (pintype "passive"))
      (node (ref "RST") (pin "2") (pinfunction "2_2") (pintype "passive"))
      (node (ref "TF1") (pin "10") (pinfunction "GND_10") (pintype "passive"))
      (node (ref "TF1") (pin "11") (pintype "passive"))
      (node (ref "TF1") (pin "12") (pintype "passive"))
      (node (ref "TF1") (pin "13") (pintype "passive"))
      (node (ref "TF1") (pin "6") (pinfunction "VSS_6") (pintype "passive"))
      (node (ref "U0") (pin "22") (pinfunction "VSSIO_22") (pintype "passive"))
      (node (ref "U1") (pin "23") (pinfunction "VSS_1_23") (pintype "passive"))
      (node (ref "U1") (pin "35") (pinfunction "VSS_2_35") (pintype "passive"))
      (node (ref "U1") (pin "47") (pinfunction "VSS_3_47") (pintype "passive"))
      (node (ref "U1") (pin "8") (pinfunction "VSSA_8") (pintype "passive"))
      (node (ref "U2") (pin "2") (pinfunction "GND_2") (pintype "passive"))
      (node (ref "U3") (pin "7") (pinfunction "GND_7") (pintype "passive"))
      (node (ref "U4") (pin "4") (pinfunction "GND_4") (pintype "passive"))
      (node (ref "USB") (pin "5") (pinfunction "GND_5") (pintype "passive"))
      (node (ref "USB") (pin "6") (pinfunction "Shell1_6") (pintype "passive"))
      (node (ref "USB") (pin "7") (pinfunction "Shell2_7") (pintype "passive"))
      (node (ref "USB") (pin "8") (pinfunction "Shell3_8") (pintype "passive"))
      (node (ref "USB") (pin "9") (pinfunction "Shell4_9") (pintype "passive"))
      (node (ref "USB_FS") (pin "5") (pinfunction "GND_5") (pintype "passive"))
      (node (ref "USB_FS") (pin "6") (pinfunction "Shell1_6") (pintype "passive"))
      (node (ref "USB_FS") (pin "7") (pinfunction "Shell2_7") (pintype "passive"))
      (node (ref "USB_FS") (pin "8") (pinfunction "Shell3_8") (pintype "passive"))
      (node (ref "USB_FS") (pin "9") (pinfunction "Shell4_9") (pintype "passive"))
      (node (ref "Y1") (pin "2") (pinfunction "GND_2") (pintype "passive"))
      (node (ref "Y5") (pin "2") (pinfunction "GND_2") (pintype "passive"))
      (node (ref "Y5") (pin "4") (pinfunction "GND_4") (pintype "passive"))
    )
    (net (code "73") (name "Net-(BL-RF_ANT)") (class "Default")
      (node (ref "BL") (pin "1") (pinfunction "RF_ANT_1") (pintype "passive"))
      (node (ref "C41") (pin "2") (pintype "passive"))
    )
    (net (code "74") (name "Net-(BLE_B-A)") (class "Default")
      (node (ref "BLE_B") (pin "1") (pinfunction "A_1") (pintype "passive"))
      (node (ref "R20") (pin "2") (pintype "passive"))
    )
    (net (code "75") (name "Net-(C28-Pad2)") (class "Default")
      (node (ref "C28") (pin "2") (pintype "passive"))
      (node (ref "R18") (pin "1") (pintype "passive"))
    )
    (net (code "76") (name "Net-(C30-Pad1)") (class "Default")
      (node (ref "C30") (pin "1") (pintype "passive"))
      (node (ref "R19") (pin "1") (pintype "passive"))
    )
    (net (code "77") (name "Net-(C48-Pad1)") (class "Default")
      (node (ref "C48") (pin "1") (pintype "passive"))
      (node (ref "R30") (pin "1") (pintype "passive"))
    )
    (net (code "78") (name "Net-(C49-Pad1)") (class "Default")
      (node (ref "C49") (pin "1") (pintype "passive"))
      (node (ref "R31") (pin "1") (pintype "passive"))
    )
    (net (code "79") (name "Net-(CHG-CE)") (class "Default")
      (node (ref "C25") (pin "1") (pinfunction "1_1") (pintype "passive"))
      (node (ref "CHG") (pin "4") (pinfunction "VCC_4") (pintype "passive"))
      (node (ref "CHG") (pin "8") (pinfunction "CE_8") (pintype "passive"))
      (node (ref "R13") (pin "1") (pintype "passive"))
      (node (ref "R14") (pin "1") (pintype "passive"))
      (node (ref "R15") (pin "1") (pintype "passive"))
    )
    (net (code "80") (name "Net-(CHG-CHRG)") (class "Default")
      (node (ref "CHG") (pin "7") (pinfunction "CHRG_7") (pintype "passive"))
      (node (ref "DS_R") (pin "2") (pinfunction "K_2") (pintype "passive"))
    )
    (net (code "81") (name "Net-(CHG-PROG)") (class "Default")
      (node (ref "CHG") (pin "2") (pinfunction "PROG_2") (pintype "passive"))
      (node (ref "R16") (pin "2") (pintype "passive"))
    )
    (net (code "82") (name "Net-(CHG-STDBY)") (class "Default")
      (node (ref "CHG") (pin "6") (pinfunction "STDBY_6") (pintype "passive"))
      (node (ref "DS_G") (pin "2") (pinfunction "K_2") (pintype "passive"))
    )
    (net (code "83") (name "Net-(DS_G-A)") (class "Default")
      (node (ref "DS_G") (pin "1") (pinfunction "A_1") (pintype "passive"))
      (node (ref "R14") (pin "2") (pintype "passive"))
    )
    (net (code "84") (name "Net-(DS_R-A)") (class "Default")
      (node (ref "DS_R") (pin "1") (pinfunction "A_1") (pintype "passive"))
      (node (ref "R13") (pin "2") (pintype "passive"))
    )
    (net (code "85") (name "Net-(FM-Pad1)") (class "Default")
      (node (ref "FM") (pin "1") (pinfunction "1_1") (pintype "passive"))
      (node (ref "L1") (pin "2") (pintype "passive"))
    )
    (net (code "86") (name "Net-(MODE-Pad1)") (class "Default")
      (node (ref "MODE") (pin "1") (pinfunction "1_1") (pintype "passive"))
      (node (ref "R38") (pin "2") (pintype "passive"))
    )
    (net (code "87") (name "Net-(NEXT-Pad1)") (class "Default")
      (node (ref "NEXT") (pin "1") (pinfunction "1_1") (pintype "passive"))
      (node (ref "R37") (pin "2") (pintype "passive"))
    )
    (net (code "88") (name "Net-(OLED1-C1N)") (class "Default")
      (node (ref "C18") (pin "1") (pintype "passive"))
      (node (ref "OLED1") (pin "5") (pinfunction "C1N_5") (pintype "passive"))
    )
    (net (code "89") (name "Net-(OLED1-C1P)") (class "Default")
      (node (ref "C18") (pin "2") (pintype "passive"))
      (node (ref "OLED1") (pin "4") (pinfunction "C1P_4") (pintype "passive"))
    )
    (net (code "90") (name "Net-(OLED1-C2N)") (class "Default")
      (node (ref "C17") (pin "1") (pintype "passive"))
      (node (ref "OLED1") (pin "3") (pinfunction "C2N_3") (pintype "passive"))
    )
    (net (code "91") (name "Net-(OLED1-C2P)") (class "Default")
      (node (ref "C17") (pin "2") (pintype "passive"))
      (node (ref "OLED1") (pin "2") (pinfunction "C2P_2") (pintype "passive"))
    )
    (net (code "92") (name "Net-(OLED1-IREF)") (class "Default")
      (node (ref "OLED1") (pin "26") (pinfunction "IREF_26") (pintype "passive"))
      (node (ref "R12") (pin "2") (pintype "passive"))
    )
    (net (code "93") (name "Net-(OLED1-VCC)") (class "Default")
      (node (ref "C21") (pin "2") (pintype "passive"))
      (node (ref "C22") (pin "2") (pintype "passive"))
      (node (ref "OLED1") (pin "28") (pinfunction "VCC_28") (pintype "passive"))
    )
    (net (code "94") (name "Net-(OLED1-VCOMH)") (class "Default")
      (node (ref "C23") (pin "2") (pintype "passive"))
      (node (ref "OLED1") (pin "27") (pinfunction "VCOMH_27") (pintype "passive"))
    )
    (net (code "95") (name "Net-(PLAY-Pad1)") (class "Default")
      (node (ref "PLAY") (pin "1") (pinfunction "1_1") (pintype "passive"))
      (node (ref "R39") (pin "1") (pintype "passive"))
    )
    (net (code "96") (name "Net-(PREV-Pad1)") (class "Default")
      (node (ref "PREV") (pin "1") (pinfunction "1_1") (pintype "passive"))
      (node (ref "R36") (pin "2") (pintype "passive"))
    )
    (net (code "97") (name "Net-(TF1-SW_DECT)") (class "Default")
      (node (ref "R26") (pin "1") (pintype "passive"))
      (node (ref "TF1") (pin "9") (pinfunction "SW_DECT_9") (pintype "passive"))
    )
    (net (code "98") (name "Net-(U1-VBAT)") (class "Default")
      (node (ref "C11") (pin "1") (pinfunction "1_1") (pintype "passive"))
      (node (ref "D1") (pin "2") (pintype "passive"))
      (node (ref "U1") (pin "1") (pinfunction "VBAT_1") (pintype "passive"))
    )
    (net (code "99") (name "Net-(U2-BYP)") (class "Default")
      (node (ref "C16") (pin "2") (pintype "passive"))
      (node (ref "U2") (pin "4") (pinfunction "BYP_4") (pintype "passive"))
    )
    (net (code "100") (name "Net-(U3-BYPASS)") (class "Default")
      (node (ref "C29") (pin "2") (pintype "passive"))
      (node (ref "U3") (pin "2") (pinfunction "BYPASS_2") (pintype "passive"))
    )
    (net (code "101") (name "Net-(U3-IN+)") (class "Default")
      (node (ref "R19") (pin "2") (pintype "passive"))
      (node (ref "U3") (pin "4") (pinfunction "IN+_4") (pintype "passive"))
    )
    (net (code "102") (name "Net-(U3-IN-)") (class "Default")
      (node (ref "R18") (pin "2") (pintype "passive"))
      (node (ref "U3") (pin "3") (pinfunction "IN-_3") (pintype "passive"))
    )
    (net (code "103") (name "Net-(U3-OUT+)") (class "Default")
      (node (ref "SP+") (pin "1") (pinfunction "1_1") (pintype "passive"))
      (node (ref "U3") (pin "5") (pinfunction "OUT+_5") (pintype "passive"))
    )
    (net (code "104") (name "Net-(U3-OUT-)") (class "Default")
      (node (ref "SP-") (pin "1") (pinfunction "1_1") (pintype "passive"))
      (node (ref "U3") (pin "8") (pinfunction "OUT-_8") (pintype "passive"))
    )
    (net (code "105") (name "Net-(U4-INA+)") (class "Default")
      (node (ref "U4") (pin "3") (pinfunction "INA+_3") (pintype "passive"))
      (node (ref "U4") (pin "6") (pinfunction "INB-_6") (pintype "passive"))
      (node (ref "U4") (pin "7") (pinfunction "OUTB_7") (pintype "passive"))
    )
    (net (code "106") (name "Net-(U4-INA-)") (class "Default")
      (node (ref "R22") (pin "1") (pintype "passive"))
      (node (ref "R23") (pin "1") (pintype "passive"))
      (node (ref "U4") (pin "2") (pinfunction "INA-_2") (pintype "passive"))
    )
    (net (code "107") (name "Net-(U4-INB+)") (class "Default")
      (node (ref "C33") (pin "2") (pintype "passive"))
      (node (ref "R21") (pin "2") (pintype "passive"))
      (node (ref "R46") (pin "1") (pintype "passive"))
      (node (ref "U4") (pin "5") (pinfunction "INB+_5") (pintype "passive"))
    )
    (net (code "108") (name "Net-(U4-OUTA)") (class "Default")
      (node (ref "C34") (pin "1") (pintype "passive"))
      (node (ref "R23") (pin "2") (pintype "passive"))
      (node (ref "U4") (pin "1") (pinfunction "OUTA_1") (pintype "passive"))
    )
    (net (code "109") (name "Net-(USB-D+)") (class "Default")
      (node (ref "R29") (pin "2") (pintype "passive"))
      (node (ref "R9") (pin "1") (pintype "passive"))
      (node (ref "USB") (pin "3") (pinfunction "D+_3") (pintype "passive"))
    )
    (net (code "110") (name "Net-(USB-D-)") (class "Default")
      (node (ref "R8") (pin "1") (pintype "passive"))
      (node (ref "USB") (pin "2") (pinfunction "D-_2") (pintype "passive"))
    )
    (net (code "111") (name "VCC3.3") (class "Default")
      (node (ref "C10") (pin "2") (pintype "passive"))
      (node (ref "C14") (pin "2") (pintype "passive"))
      (node (ref "C15") (pin "2") (pintype "passive"))
      (node (ref "C19") (pin "2") (pintype "passive"))
      (node (ref "C20") (pin "2") (pintype "passive"))
      (node (ref "C31") (pin "2") (pintype "passive"))
      (node (ref "C32") (pin "2") (pintype "passive"))
      (node (ref "C6") (pin "2") (pintype "passive"))
      (node (ref "C7") (pin "2") (pintype "passive"))
      (node (ref "C8") (pin "2") (pintype "passive"))
      (node (ref "C9") (pin "2") (pintype "passive"))
      (node (ref "H1") (pin "4") (pinfunction "4_4") (pintype "passive"))
      (node (ref "H5") (pin "1") (pinfunction "1_1") (pintype "passive"))
      (node (ref "KEY0") (pin "1") (pinfunction "1_1") (pintype "passive"))
      (node (ref "OLED1") (pin "11") (pinfunction "BS1_11") (pintype "passive"))
      (node (ref "OLED1") (pin "12") (pinfunction "BS2_12") (pintype "passive"))
      (node (ref "OLED1") (pin "6") (pinfunction "VBAT_6") (pintype "passive"))
      (node (ref "OLED1") (pin "9") (pinfunction "VDD_9") (pintype "passive"))
      (node (ref "R1") (pin "1") (pintype "passive"))
      (node (ref "R29") (pin "1") (pintype "passive"))
      (node (ref "R3") (pin "1") (pintype "passive"))
      (node (ref "R4") (pin "2") (pintype "passive"))
      (node (ref "R45") (pin "2") (pintype "passive"))
      (node (ref "R46") (pin "2") (pintype "passive"))
      (node (ref "U1") (pin "24") (pinfunction "VDD_1_24") (pintype "passive"))
      (node (ref "U1") (pin "36") (pinfunction "VDD_2_36") (pintype "passive"))
      (node (ref "U1") (pin "48") (pinfunction "VDD_3_48") (pintype "passive"))
      (node (ref "U2") (pin "5") (pinfunction "OUT_5") (pintype "passive"))
      (node (ref "U4") (pin "8") (pinfunction "VCC_8") (pintype "passive"))
    )
    (net (code "112") (name "VCCA3.3") (class "Default")
      (node (ref "C36") (pin "2") (pintype "passive"))
      (node (ref "C39") (pin "1") (pintype "passive"))
      (node (ref "R35") (pin "1") (pintype "passive"))
      (node (ref "TF1") (pin "4") (pinfunction "VDD_4") (pintype "passive"))
      (node (ref "U0") (pin "12") (pinfunction "VDDIO_12") (pintype "passive"))
    )
    (net (code "113") (name "VUSB") (class "Default")
      (node (ref "R15") (pin "2") (pintype "passive"))
      (node (ref "USB") (pin "1") (pinfunction "VCC_1") (pintype "passive"))
    )
    (net (code "114") (name "unconnected-(OLED1-NC(VBREF)-Pad7)") (class "Default")
      (node (ref "OLED1") (pin "7") (pinfunction "NC(VBREF)_7") (pintype "passive"))
    )
    (net (code "115") (name "unconnected-(POWER-GND-Pad4)") (class "Default")
      (node (ref "POWER") (pin "4") (pinfunction "GND_4") (pintype "passive"))
    )
    (net (code "116") (name "unconnected-(POWER-GND-Pad5)") (class "Default")
      (node (ref "POWER") (pin "5") (pinfunction "GND_5") (pintype "passive"))
    )
    (net (code "117") (name "unconnected-(POWER-I{slash}O-Pad1)") (class "Default")
      (node (ref "POWER") (pin "1") (pinfunction "I/O_1") (pintype "passive"))
    )
    (net (code "118") (name "unconnected-(TF1-DAT1-Pad8)") (class "Default")
      (node (ref "TF1") (pin "8") (pinfunction "DAT1_8") (pintype "passive"))
    )
    (net (code "119") (name "unconnected-(TF1-DAT2-Pad1)") (class "Default")
      (node (ref "TF1") (pin "1") (pinfunction "DAT2_1") (pintype "passive"))
    )
    (net (code "120") (name "unconnected-(TF1-DAT3-Pad2)") (class "Default")
      (node (ref "TF1") (pin "2") (pinfunction "DAT3_2") (pintype "passive"))
    )
    (net (code "121") (name "unconnected-(USB-ID-Pad4)") (class "Default")
      (node (ref "USB") (pin "4") (pinfunction "ID_4") (pintype "passive"))
    )
    (net (code "122") (name "unconnected-(USB_FS-ID-Pad4)") (class "Default")
      (node (ref "USB_FS") (pin "4") (pinfunction "ID_4") (pintype "passive"))
    )
  )
)
